# PUSHBUTTON-DEBOUNCE-INTERFACE.net
KiCad netlist of a schematic drawn in EAGLE
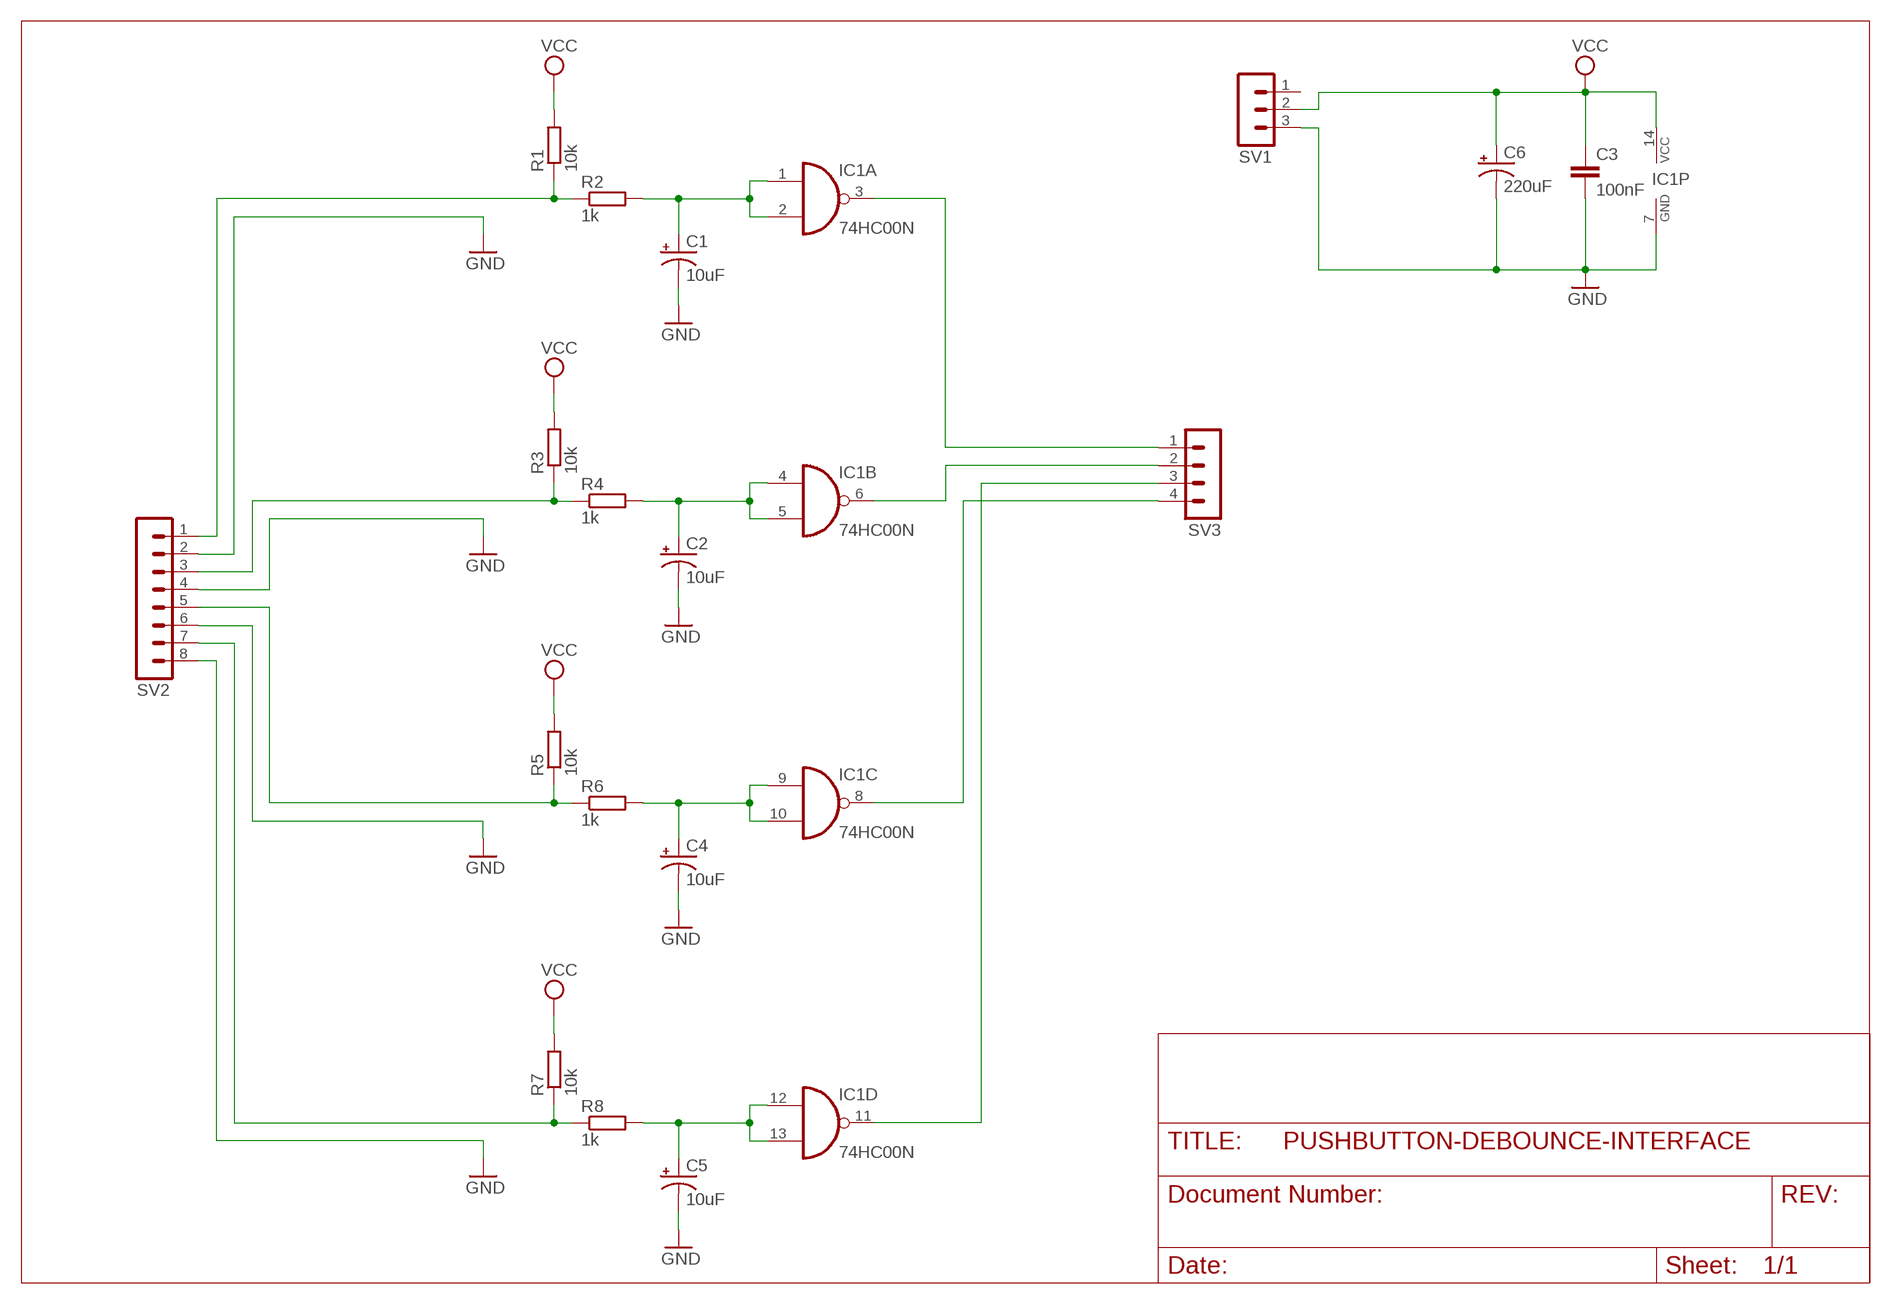
[diagram p0: schematic, sheet 1]

(export (version "E")
  (design (tool "Eeschema 10.0.6"))
  (components
    (comp (ref "C1")
      (value "10uF")
      (footprint "eagle-import:CPOL-RADIAL-100UF-25V")
      (libsource (lib "eagle-import") (part "CAP_POLPTH1"))
    )
    (comp (ref "C2")
      (value "10uF")
      (footprint "eagle-import:CPOL-RADIAL-100UF-25V")
      (libsource (lib "eagle-import") (part "CAP_POLPTH1"))
    )
    (comp (ref "C3")
      (value "100nF")
      (footprint "eagle-import:CAP-PTH-SMALL")
      (libsource (lib "eagle-import") (part "CAPPTH"))
    )
    (comp (ref "C4")
      (value "10uF")
      (footprint "eagle-import:CPOL-RADIAL-100UF-25V")
      (libsource (lib "eagle-import") (part "CAP_POLPTH1"))
    )
    (comp (ref "C5")
      (value "10uF")
      (footprint "eagle-import:CPOL-RADIAL-100UF-25V")
      (libsource (lib "eagle-import") (part "CAP_POLPTH1"))
    )
    (comp (ref "C6")
      (value "220uF")
      (footprint "eagle-import:CPOL-RADIAL-1000UF-25V")
      (libsource (lib "eagle-import") (part "CAP_POLPTH4"))
    )
    (comp (ref "IC1")
      (value "74HC00N")
      (footprint "eagle-import:DIL14")
      (libsource (lib "eagle-import") (part "7400NHC"))
    )
    (comp (ref "R1")
      (value "10k")
      (footprint "eagle-import:0207_7")
      (libsource (lib "eagle-import") (part "resistor_R-EU_0207/7"))
    )
    (comp (ref "R2")
      (value "1k")
      (footprint "eagle-import:0207_7")
      (libsource (lib "eagle-import") (part "resistor_R-EU_0207/7"))
    )
    (comp (ref "R3")
      (value "10k")
      (footprint "eagle-import:0207_12")
      (libsource (lib "eagle-import") (part "R-EU_0207/12"))
    )
    (comp (ref "R4")
      (value "1k")
      (footprint "eagle-import:0207_7")
      (libsource (lib "eagle-import") (part "resistor_R-EU_0207/7"))
    )
    (comp (ref "R5")
      (value "10k")
      (footprint "eagle-import:0207_12")
      (libsource (lib "eagle-import") (part "R-EU_0207/12"))
    )
    (comp (ref "R6")
      (value "1k")
      (footprint "eagle-import:0207_7")
      (libsource (lib "eagle-import") (part "resistor_R-EU_0207/7"))
    )
    (comp (ref "R7")
      (value "10k")
      (footprint "eagle-import:0207_7")
      (libsource (lib "eagle-import") (part "resistor_R-EU_0207/7"))
    )
    (comp (ref "R8")
      (value "1k")
      (footprint "eagle-import:0207_7")
      (libsource (lib "eagle-import") (part "resistor_R-EU_0207/7"))
    )
    (comp (ref "SV1")
      (value "MA03-1")
      (footprint "eagle-import:MA03-1")
      (libsource (lib "eagle-import") (part "MA03-1"))
    )
    (comp (ref "SV2")
      (value "MA08-1")
      (footprint "eagle-import:MA08-1")
      (libsource (lib "eagle-import") (part "MA08-1"))
    )
    (comp (ref "SV3")
      (value "MA04-1")
      (footprint "eagle-import:MA04-1")
      (libsource (lib "eagle-import") (part "MA04-1"))
    )
  )
  (nets
    (net (code "1") (name "GND") (class "Default")
      (node (ref "C1") (pin "2") (pinfunction "-_2") (pintype "passive"))
      (node (ref "C2") (pin "2") (pinfunction "-_2") (pintype "passive"))
      (node (ref "C3") (pin "2") (pinfunction "2_2") (pintype "passive"))
      (node (ref "C4") (pin "2") (pinfunction "-_2") (pintype "passive"))
      (node (ref "C5") (pin "2") (pinfunction "-_2") (pintype "passive"))
      (node (ref "C6") (pin "2") (pinfunction "-_2") (pintype "passive"))
      (node (ref "IC1") (pin "7") (pinfunction "GND_7") (pintype "power_in"))
      (node (ref "SV1") (pin "3") (pinfunction "3_3") (pintype "passive"))
      (node (ref "SV2") (pin "2") (pinfunction "2_2") (pintype "passive"))
      (node (ref "SV2") (pin "4") (pinfunction "4_4") (pintype "passive"))
      (node (ref "SV2") (pin "6") (pinfunction "6_6") (pintype "passive"))
      (node (ref "SV2") (pin "8") (pinfunction "8_8") (pintype "passive"))
    )
    (net (code "2") (name "Net-(C1-+)") (class "Default")
      (node (ref "C1") (pin "1") (pinfunction "+_1") (pintype "passive"))
      (node (ref "IC1") (pin "1") (pinfunction "I0_1") (pintype "input"))
      (node (ref "IC1") (pin "2") (pinfunction "I1_2") (pintype "input"))
      (node (ref "R2") (pin "2") (pinfunction "2_2") (pintype "passive"))
    )
    (net (code "3") (name "Net-(C2-+)") (class "Default")
      (node (ref "C2") (pin "1") (pinfunction "+_1") (pintype "passive"))
      (node (ref "IC1") (pin "4") (pinfunction "I0_4") (pintype "input"))
      (node (ref "IC1") (pin "5") (pinfunction "I1_5") (pintype "input"))
      (node (ref "R4") (pin "2") (pinfunction "2_2") (pintype "passive"))
    )
    (net (code "4") (name "Net-(C4-+)") (class "Default")
      (node (ref "C4") (pin "1") (pinfunction "+_1") (pintype "passive"))
      (node (ref "IC1") (pin "10") (pinfunction "I1_10") (pintype "input"))
      (node (ref "IC1") (pin "9") (pinfunction "I0_9") (pintype "input"))
      (node (ref "R6") (pin "2") (pinfunction "2_2") (pintype "passive"))
    )
    (net (code "5") (name "Net-(C5-+)") (class "Default")
      (node (ref "C5") (pin "1") (pinfunction "+_1") (pintype "passive"))
      (node (ref "IC1") (pin "12") (pinfunction "I0_12") (pintype "input"))
      (node (ref "IC1") (pin "13") (pinfunction "I1_13") (pintype "input"))
      (node (ref "R8") (pin "2") (pinfunction "2_2") (pintype "passive"))
    )
    (net (code "6") (name "Net-(IC1A-O)") (class "Default")
      (node (ref "IC1") (pin "3") (pinfunction "O_3") (pintype "output"))
      (node (ref "SV3") (pin "1") (pinfunction "1_1") (pintype "passive"))
    )
    (net (code "7") (name "Net-(IC1B-O)") (class "Default")
      (node (ref "IC1") (pin "6") (pinfunction "O_6") (pintype "output"))
      (node (ref "SV3") (pin "2") (pinfunction "2_2") (pintype "passive"))
    )
    (net (code "8") (name "Net-(IC1C-O)") (class "Default")
      (node (ref "IC1") (pin "8") (pinfunction "O_8") (pintype "output"))
      (node (ref "SV3") (pin "4") (pinfunction "4_4") (pintype "passive"))
    )
    (net (code "9") (name "Net-(IC1D-O)") (class "Default")
      (node (ref "IC1") (pin "11") (pinfunction "O_11") (pintype "output"))
      (node (ref "SV3") (pin "3") (pinfunction "3_3") (pintype "passive"))
    )
    (net (code "10") (name "Net-(R1-Pad1)") (class "Default")
      (node (ref "R1") (pin "1") (pinfunction "1_1") (pintype "passive"))
      (node (ref "R2") (pin "1") (pinfunction "1_1") (pintype "passive"))
      (node (ref "SV2") (pin "1") (pinfunction "1_1") (pintype "passive"))
    )
    (net (code "11") (name "Net-(R3-Pad1)") (class "Default")
      (node (ref "R3") (pin "1") (pinfunction "1_1") (pintype "passive"))
      (node (ref "R4") (pin "1") (pinfunction "1_1") (pintype "passive"))
      (node (ref "SV2") (pin "3") (pinfunction "3_3") (pintype "passive"))
    )
    (net (code "12") (name "Net-(R5-Pad1)") (class "Default")
      (node (ref "R5") (pin "1") (pinfunction "1_1") (pintype "passive"))
      (node (ref "R6") (pin "1") (pinfunction "1_1") (pintype "passive"))
      (node (ref "SV2") (pin "5") (pinfunction "5_5") (pintype "passive"))
    )
    (net (code "13") (name "Net-(R7-Pad1)") (class "Default")
      (node (ref "R7") (pin "1") (pinfunction "1_1") (pintype "passive"))
      (node (ref "R8") (pin "1") (pinfunction "1_1") (pintype "passive"))
      (node (ref "SV2") (pin "7") (pinfunction "7_7") (pintype "passive"))
    )
    (net (code "14") (name "VCC") (class "Default")
      (node (ref "C3") (pin "1") (pinfunction "1_1") (pintype "passive"))
      (node (ref "C6") (pin "1") (pinfunction "+_1") (pintype "passive"))
      (node (ref "IC1") (pin "14") (pinfunction "VCC_14") (pintype "power_in"))
      (node (ref "R1") (pin "2") (pinfunction "2_2") (pintype "passive"))
      (node (ref "R3") (pin "2") (pinfunction "2_2") (pintype "passive"))
      (node (ref "R5") (pin "2") (pinfunction "2_2") (pintype "passive"))
      (node (ref "R7") (pin "2") (pinfunction "2_2") (pintype "passive"))
      (node (ref "SV1") (pin "2") (pinfunction "2_2") (pintype "passive"))
    )
    (net (code "15") (name "unconnected-(SV1-Pad1)") (class "Default")
      (node (ref "SV1") (pin "1") (pinfunction "1_1") (pintype "passive"))
    )
  )
)
